# flower.net
KiCad netlist of a schematic drawn in EAGLE
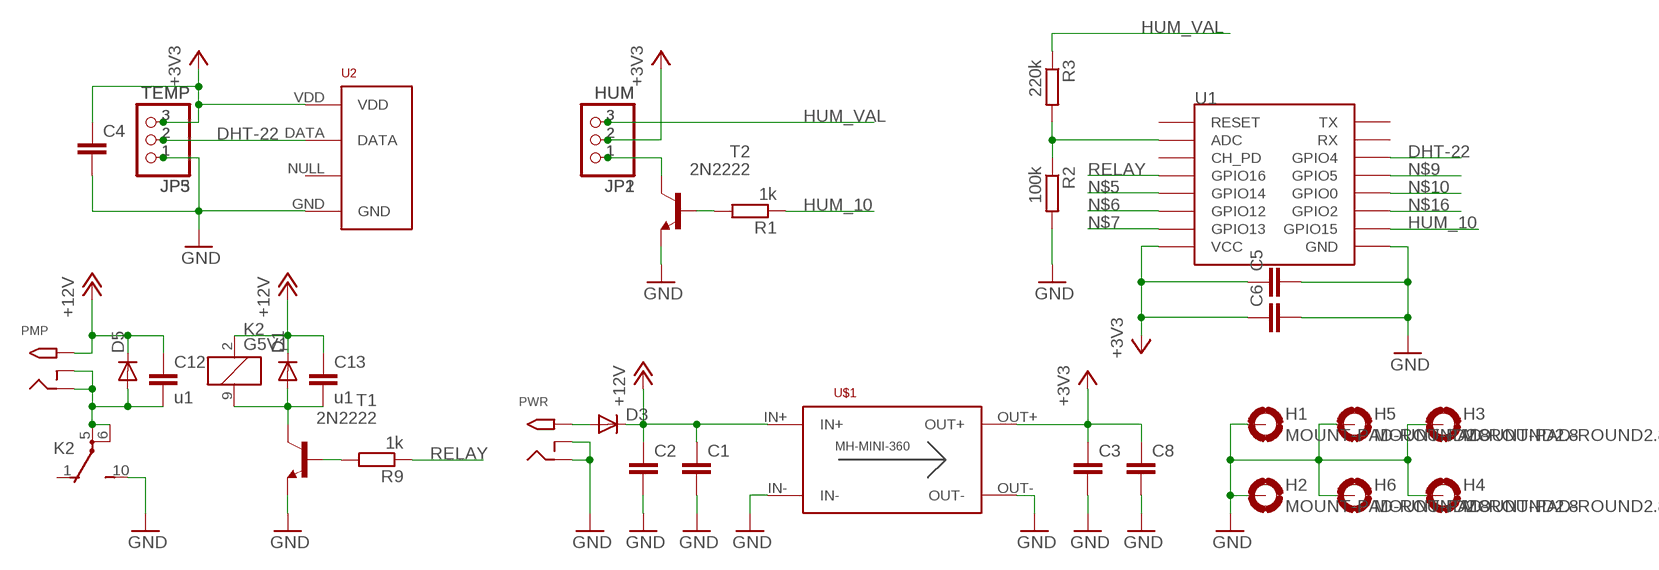
[diagram p0: schematic, sheet 1]

(export (version "E")
  (design (tool "Eeschema 10.0.6"))
  (components
    (comp (ref "C1")
      (value "C-EU025-025X050")
      (footprint "eagle-import:C025-025X050")
      (libsource (lib "eagle-import") (part "C-EU025-025X050"))
    )
    (comp (ref "C2")
      (value "C-EUC0805K")
      (footprint "eagle-import:C0805K")
      (libsource (lib "eagle-import") (part "C-EUC0805K"))
    )
    (comp (ref "C3")
      (value "C-EU025-025X050")
      (footprint "eagle-import:C025-025X050")
      (libsource (lib "eagle-import") (part "C-EU025-025X050"))
    )
    (comp (ref "C4")
      (value "C-EU025-025X050")
      (footprint "eagle-import:C025-025X050")
      (libsource (lib "eagle-import") (part "C-EU025-025X050"))
    )
    (comp (ref "C5")
      (value "C-EU025-025X050")
      (footprint "eagle-import:C025-025X050")
      (libsource (lib "eagle-import") (part "C-EU025-025X050"))
    )
    (comp (ref "C6")
      (value "C-EU025-025X050")
      (footprint "eagle-import:C025-025X050")
      (libsource (lib "eagle-import") (part "C-EU025-025X050"))
    )
    (comp (ref "C8")
      (value "C-EUC0805K")
      (footprint "eagle-import:C0805K")
      (libsource (lib "eagle-import") (part "C-EUC0805K"))
    )
    (comp (ref "C12")
      (value "u1")
      (footprint "eagle-import:C025-025X050")
      (libsource (lib "eagle-import") (part "C-EU025-025X050"))
    )
    (comp (ref "C13")
      (value "u1")
      (footprint "eagle-import:C025-025X050")
      (libsource (lib "eagle-import") (part "C-EU025-025X050"))
    )
    (comp (ref "D1")
      (value "DIODE-D-5")
      (footprint "eagle-import:D-5")
      (libsource (lib "eagle-import") (part "DIODE-D-5"))
    )
    (comp (ref "D3")
      (value "DIODE-D-5")
      (footprint "eagle-import:D-5")
      (libsource (lib "eagle-import") (part "DIODE-D-5"))
    )
    (comp (ref "D5")
      (value "DIODE-D-5")
      (footprint "eagle-import:D-5")
      (libsource (lib "eagle-import") (part "DIODE-D-5"))
    )
    (comp (ref "H1")
      (value "MOUNT-PAD-ROUND2.8")
      (footprint "eagle-import:2,8-PAD")
      (libsource (lib "eagle-import") (part "MOUNT-PAD-ROUND2.8"))
    )
    (comp (ref "H2")
      (value "MOUNT-PAD-ROUND2.8")
      (footprint "eagle-import:2,8-PAD")
      (libsource (lib "eagle-import") (part "MOUNT-PAD-ROUND2.8"))
    )
    (comp (ref "H3")
      (value "MOUNT-PAD-ROUND2.8")
      (footprint "eagle-import:2,8-PAD")
      (libsource (lib "eagle-import") (part "MOUNT-PAD-ROUND2.8"))
    )
    (comp (ref "H4")
      (value "MOUNT-PAD-ROUND2.8")
      (footprint "eagle-import:2,8-PAD")
      (libsource (lib "eagle-import") (part "MOUNT-PAD-ROUND2.8"))
    )
    (comp (ref "H5")
      (value "MOUNT-PAD-ROUND2.8")
      (footprint "eagle-import:2,8-PAD")
      (libsource (lib "eagle-import") (part "MOUNT-PAD-ROUND2.8"))
    )
    (comp (ref "H6")
      (value "MOUNT-PAD-ROUND2.8")
      (footprint "eagle-import:2,8-PAD")
      (libsource (lib "eagle-import") (part "MOUNT-PAD-ROUND2.8"))
    )
    (comp (ref "JP1")
      (value "HUM")
      (footprint "eagle-import:1X03_90")
      (libsource (lib "eagle-import") (part "PINHD-1X3/90"))
    )
    (comp (ref "JP2")
      (value "HUM")
      (footprint "eagle-import:1X03")
      (libsource (lib "eagle-import") (part "PINHD-1X3"))
    )
    (comp (ref "JP3")
      (value "TEMP")
      (footprint "eagle-import:1X03")
      (libsource (lib "eagle-import") (part "PINHD-1X3"))
    )
    (comp (ref "JP5")
      (value "TEMP")
      (footprint "eagle-import:1X03_90")
      (libsource (lib "eagle-import") (part "PINHD-1X3/90"))
    )
    (comp (ref "K2")
      (value "G5V1")
      (footprint "eagle-import:G5V1")
      (fields (field (name "MPN") "G5V-1-DC24"))
      (libsource (lib "eagle-import") (part "G5V1"))
    )
    (comp (ref "PMP")
      (value "PMP")
      (footprint "eagle-import:PJ-102A")
      (libsource (lib "eagle-import") (part "2.1MMJACKTHM"))
    )
    (comp (ref "PWR")
      (value "PWR")
      (footprint "eagle-import:PJ-102A")
      (libsource (lib "eagle-import") (part "2.1MMJACKTHM"))
    )
    (comp (ref "R1")
      (value "1k")
      (footprint "eagle-import:0204_7")
      (libsource (lib "eagle-import") (part "R-EU_0204/7"))
    )
    (comp (ref "R2")
      (value "100k")
      (footprint "eagle-import:0204_7")
      (libsource (lib "eagle-import") (part "R-EU_0204/7"))
    )
    (comp (ref "R3")
      (value "220k")
      (footprint "eagle-import:0204_7")
      (libsource (lib "eagle-import") (part "R-EU_0204/7"))
    )
    (comp (ref "R9")
      (value "1k")
      (footprint "eagle-import:0207_10")
      (libsource (lib "eagle-import") (part "R-EU_0207/10"))
    )
    (comp (ref "T1")
      (value "2N2222")
      (footprint "eagle-import:TO92-EBC-OVAL")
      (libsource (lib "eagle-import") (part "2N2222"))
    )
    (comp (ref "T2")
      (value "2N2222")
      (footprint "eagle-import:TO92-EBC-OVAL")
      (libsource (lib "eagle-import") (part "2N2222"))
    )
    (comp (ref "U$1")
      (value "DC-DC_CONV_MINISTD")
      (footprint "eagle-import:DC-DC_CONV_MINI")
      (libsource (lib "eagle-import") (part "DC-DC_CONV_MINISTD"))
    )
    (comp (ref "U1")
      (value "ESP12EDIP")
      (footprint "eagle-import:ESP-12-BREAKOUT")
      (libsource (lib "eagle-import") (part "ESP12EDIP"))
    )
    (comp (ref "U2")
      (value "RHT03_DHT-22_AM2302RA")
      (footprint "eagle-import:RHT03_DHT-22_RA")
      (libsource (lib "eagle-import") (part "RHT03_DHT-22_AM2302RA"))
    )
  )
  (nets
    (net (code "1") (name "+3V3") (class "Default")
      (node (ref "C3") (pin "1") (pinfunction "1_1") (pintype "passive"))
      (node (ref "C4") (pin "1") (pinfunction "1_1") (pintype "passive"))
      (node (ref "C5") (pin "1") (pinfunction "1_1") (pintype "passive"))
      (node (ref "C6") (pin "1") (pinfunction "1_1") (pintype "passive"))
      (node (ref "C8") (pin "1") (pinfunction "1_1") (pintype "passive"))
      (node (ref "JP1") (pin "2") (pinfunction "2_2") (pintype "passive"))
      (node (ref "JP2") (pin "2") (pinfunction "2_2") (pintype "passive"))
      (node (ref "JP3") (pin "3") (pinfunction "3_3") (pintype "passive"))
      (node (ref "JP5") (pin "3") (pinfunction "3_3") (pintype "passive"))
      (node (ref "U$1") (pin "OUT+") (pinfunction "OUT+_OUT+") (pintype "bidirectional"))
      (node (ref "U1") (pin "P$1") (pinfunction "VCC_P$1") (pintype "bidirectional"))
      (node (ref "U2") (pin "VDD") (pinfunction "VDD_VDD") (pintype "power_in"))
    )
    (net (code "2") (name "+12V") (class "Default")
      (node (ref "C1") (pin "1") (pinfunction "1_1") (pintype "passive"))
      (node (ref "C12") (pin "1") (pinfunction "1_1") (pintype "passive"))
      (node (ref "C13") (pin "1") (pinfunction "1_1") (pintype "passive"))
      (node (ref "C2") (pin "1") (pinfunction "1_1") (pintype "passive"))
      (node (ref "D1") (pin "C") (pinfunction "C_C") (pintype "passive"))
      (node (ref "D3") (pin "C") (pinfunction "C_C") (pintype "passive"))
      (node (ref "D5") (pin "C") (pinfunction "C_C") (pintype "passive"))
      (node (ref "K2") (pin "2") (pinfunction "1_2") (pintype "passive"))
      (node (ref "PMP") (pin "TIP") (pinfunction "TIP_TIP") (pintype "bidirectional"))
      (node (ref "U$1") (pin "IN+") (pinfunction "IN+_IN+") (pintype "bidirectional"))
    )
    (net (code "3") (name "/DHT-22") (class "Default")
      (node (ref "JP3") (pin "2") (pinfunction "2_2") (pintype "passive"))
      (node (ref "JP5") (pin "2") (pinfunction "2_2") (pintype "passive"))
      (node (ref "U1") (pin "P$14") (pinfunction "GPIO4_P$14") (pintype "bidirectional"))
      (node (ref "U2") (pin "DATA") (pinfunction "DATA_DATA") (pintype "bidirectional"))
    )
    (net (code "4") (name "/HUM_10") (class "Default")
      (node (ref "R1") (pin "1") (pinfunction "1_1") (pintype "passive"))
      (node (ref "U1") (pin "P$10") (pinfunction "GPIO15_P$10") (pintype "bidirectional"))
    )
    (net (code "5") (name "/HUM_VAL") (class "Default")
      (node (ref "JP1") (pin "3") (pinfunction "3_3") (pintype "passive"))
      (node (ref "JP2") (pin "3") (pinfunction "3_3") (pintype "passive"))
      (node (ref "R3") (pin "1") (pinfunction "1_1") (pintype "passive"))
    )
    (net (code "6") (name "/N$5") (class "Default")
      (node (ref "U1") (pin "P$4") (pinfunction "GPIO14_P$4") (pintype "bidirectional"))
    )
    (net (code "7") (name "/N$6") (class "Default")
      (node (ref "U1") (pin "P$3") (pinfunction "GPIO12_P$3") (pintype "bidirectional"))
    )
    (net (code "8") (name "/N$7") (class "Default")
      (node (ref "U1") (pin "P$2") (pinfunction "GPIO13_P$2") (pintype "bidirectional"))
    )
    (net (code "9") (name "/N$9") (class "Default")
      (node (ref "U1") (pin "P$13") (pinfunction "GPIO5_P$13") (pintype "bidirectional"))
    )
    (net (code "10") (name "/N$10") (class "Default")
      (node (ref "U1") (pin "P$12") (pinfunction "GPIO0_P$12") (pintype "bidirectional"))
    )
    (net (code "11") (name "/N$16") (class "Default")
      (node (ref "U1") (pin "P$11") (pinfunction "GPIO2_P$11") (pintype "bidirectional"))
    )
    (net (code "12") (name "/RELAY") (class "Default")
      (node (ref "R9") (pin "1") (pinfunction "1_1") (pintype "passive"))
      (node (ref "U1") (pin "P$5") (pinfunction "GPIO16_P$5") (pintype "bidirectional"))
    )
    (net (code "13") (name "GND") (class "Default")
      (node (ref "C1") (pin "2") (pinfunction "2_2") (pintype "passive"))
      (node (ref "C2") (pin "2") (pinfunction "2_2") (pintype "passive"))
      (node (ref "C3") (pin "2") (pinfunction "2_2") (pintype "passive"))
      (node (ref "C4") (pin "2") (pinfunction "2_2") (pintype "passive"))
      (node (ref "C5") (pin "2") (pinfunction "2_2") (pintype "passive"))
      (node (ref "C6") (pin "2") (pinfunction "2_2") (pintype "passive"))
      (node (ref "C8") (pin "2") (pinfunction "2_2") (pintype "passive"))
      (node (ref "H1") (pin "B2,8") (pinfunction "MOUNT_B2,8") (pintype "passive"))
      (node (ref "H2") (pin "B2,8") (pinfunction "MOUNT_B2,8") (pintype "passive"))
      (node (ref "H3") (pin "B2,8") (pinfunction "MOUNT_B2,8") (pintype "passive"))
      (node (ref "H4") (pin "B2,8") (pinfunction "MOUNT_B2,8") (pintype "passive"))
      (node (ref "H5") (pin "B2,8") (pinfunction "MOUNT_B2,8") (pintype "passive"))
      (node (ref "H6") (pin "B2,8") (pinfunction "MOUNT_B2,8") (pintype "passive"))
      (node (ref "JP3") (pin "1") (pinfunction "1_1") (pintype "passive"))
      (node (ref "JP5") (pin "1") (pinfunction "1_1") (pintype "passive"))
      (node (ref "K2") (pin "10") (pinfunction "S_10") (pintype "passive"))
      (node (ref "PWR") (pin "RING") (pinfunction "RING_RING") (pintype "bidirectional"))
      (node (ref "PWR") (pin "RING_SW") (pinfunction "RING_SW_RING_SW") (pintype "bidirectional"))
      (node (ref "R2") (pin "2") (pinfunction "2_2") (pintype "passive"))
      (node (ref "T1") (pin "E") (pinfunction "E_E") (pintype "passive"))
      (node (ref "T2") (pin "E") (pinfunction "E_E") (pintype "passive"))
      (node (ref "U$1") (pin "IN-") (pinfunction "IN-_IN-") (pintype "bidirectional"))
      (node (ref "U$1") (pin "OUT-") (pinfunction "OUT-_OUT-") (pintype "bidirectional"))
      (node (ref "U1") (pin "P$9") (pinfunction "GND_P$9") (pintype "bidirectional"))
      (node (ref "U2") (pin "GND") (pinfunction "GND_GND") (pintype "power_in"))
    )
    (net (code "14") (name "Net-(C12-Pad2)") (class "Default")
      (node (ref "C12") (pin "2") (pinfunction "2_2") (pintype "passive"))
      (node (ref "D5") (pin "A") (pinfunction "A_A") (pintype "passive"))
      (node (ref "K2") (pin "5") (pinfunction "P_5") (pintype "passive"))
      (node (ref "K2") (pin "6") (pinfunction "P_6") (pintype "passive"))
      (node (ref "PMP") (pin "RING") (pinfunction "RING_RING") (pintype "bidirectional"))
      (node (ref "PMP") (pin "RING_SW") (pinfunction "RING_SW_RING_SW") (pintype "bidirectional"))
    )
    (net (code "15") (name "Net-(D3-PadA)") (class "Default")
      (node (ref "D3") (pin "A") (pinfunction "A_A") (pintype "passive"))
      (node (ref "PWR") (pin "TIP") (pinfunction "TIP_TIP") (pintype "bidirectional"))
    )
    (net (code "16") (name "Net-(JP1-Pad1)") (class "Default")
      (node (ref "JP1") (pin "1") (pinfunction "1_1") (pintype "passive"))
      (node (ref "JP2") (pin "1") (pinfunction "1_1") (pintype "passive"))
      (node (ref "T2") (pin "C") (pinfunction "C_C") (pintype "passive"))
    )
    (net (code "17") (name "Net-(K2A-2)") (class "Default")
      (node (ref "C13") (pin "2") (pinfunction "2_2") (pintype "passive"))
      (node (ref "D1") (pin "A") (pinfunction "A_A") (pintype "passive"))
      (node (ref "K2") (pin "9") (pinfunction "2_9") (pintype "passive"))
      (node (ref "T1") (pin "C") (pinfunction "C_C") (pintype "passive"))
    )
    (net (code "18") (name "Net-(R1-Pad2)") (class "Default")
      (node (ref "R1") (pin "2") (pinfunction "2_2") (pintype "passive"))
      (node (ref "T2") (pin "B") (pinfunction "B_B") (pintype "passive"))
    )
    (net (code "19") (name "Net-(R9-Pad2)") (class "Default")
      (node (ref "R9") (pin "2") (pinfunction "2_2") (pintype "passive"))
      (node (ref "T1") (pin "B") (pinfunction "B_B") (pintype "passive"))
    )
    (net (code "20") (name "Net-(U1-ADC)") (class "Default")
      (node (ref "R2") (pin "1") (pinfunction "1_1") (pintype "passive"))
      (node (ref "R3") (pin "2") (pinfunction "2_2") (pintype "passive"))
      (node (ref "U1") (pin "P$7") (pinfunction "ADC_P$7") (pintype "bidirectional"))
    )
    (net (code "21") (name "unconnected-(K2B-O-Pad1)") (class "Default")
      (node (ref "K2") (pin "1") (pinfunction "O_1") (pintype "passive"))
    )
    (net (code "22") (name "unconnected-(U1-CH_PD-PadP$6)") (class "Default")
      (node (ref "U1") (pin "P$6") (pinfunction "CH_PD_P$6") (pintype "bidirectional"))
    )
    (net (code "23") (name "unconnected-(U1-RESET-PadP$8)") (class "Default")
      (node (ref "U1") (pin "P$8") (pinfunction "RESET_P$8") (pintype "bidirectional"))
    )
    (net (code "24") (name "unconnected-(U1-RX-PadP$15)") (class "Default")
      (node (ref "U1") (pin "P$15") (pinfunction "RX_P$15") (pintype "bidirectional"))
    )
    (net (code "25") (name "unconnected-(U1-TX-PadP$16)") (class "Default")
      (node (ref "U1") (pin "P$16") (pinfunction "TX_P$16") (pintype "bidirectional"))
    )
    (net (code "26") (name "unconnected-(U2-PadNULL)") (class "Default")
      (node (ref "U2") (pin "NULL") (pinfunction "NULL_NULL") (pintype "no_connect"))
    )
  )
)
